# imu_ultrason_breakout.net
KiCad netlist of a schematic drawn in EAGLE
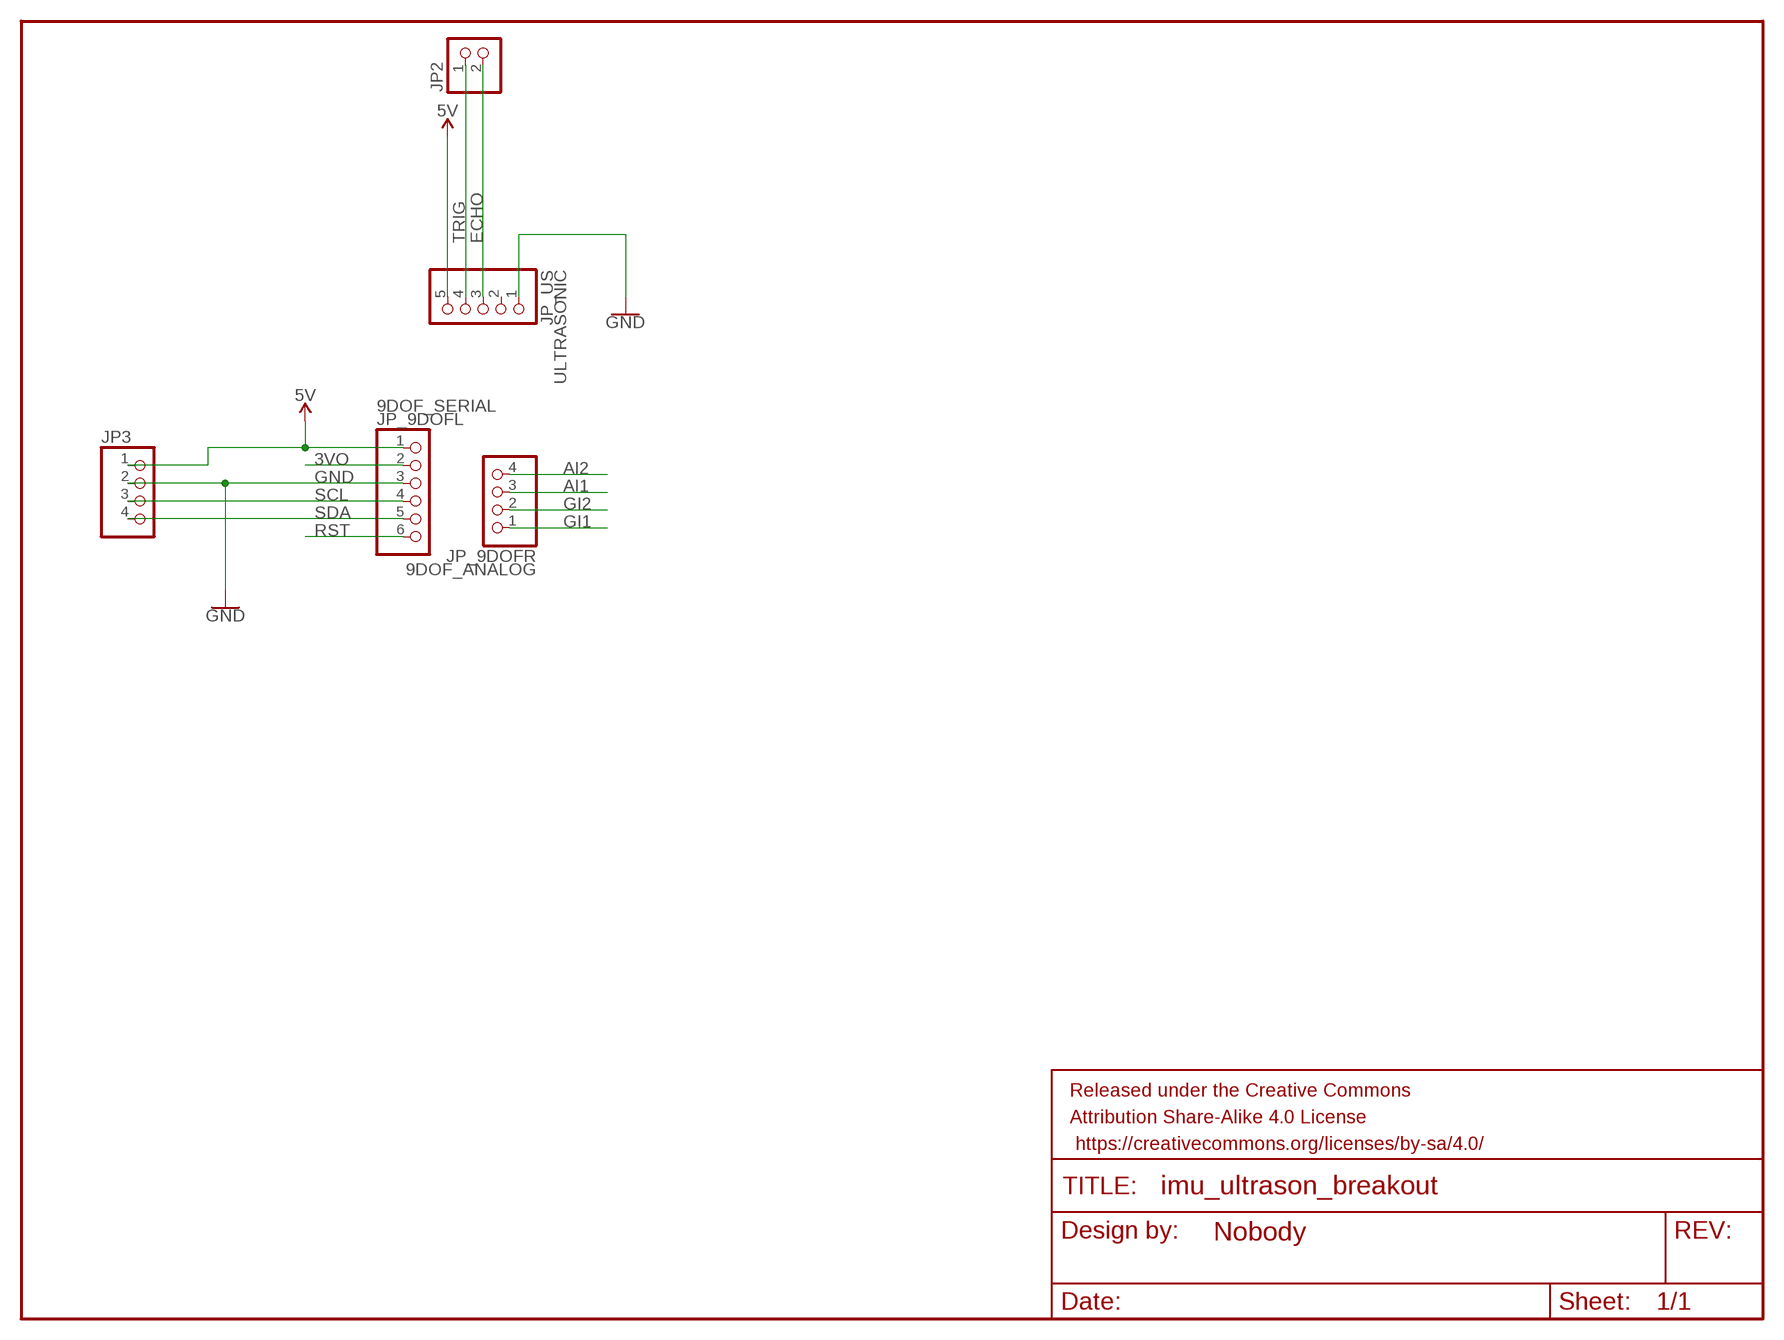
[diagram p0: schematic, sheet 1]

(export (version "E")
  (design (tool "Eeschema 10.0.6"))
  (components
    (comp (ref "FRAME1")
      (value "FRAME-LETTERNO_PACKAGE")
      (footprint "eagle-import:DUMMY")
      (fields (field (name "DESIGNER") "Nobody"))
      (libsource (lib "eagle-import") (part "FRAME-LETTERNO_PACKAGE"))
    )
    (comp (ref "JP2")
      (value "PINHD-1X2")
      (footprint "eagle-import:1X02")
      (libsource (lib "eagle-import") (part "PINHD-1X2"))
    )
    (comp (ref "JP3")
      (value "PINHD-1X4")
      (footprint "eagle-import:1X04")
      (libsource (lib "eagle-import") (part "PINHD-1X4"))
    )
    (comp (ref "JP_9DOFL")
      (value "PINHD-1X6")
      (footprint "eagle-import:1X06")
      (libsource (lib "eagle-import") (part "PINHD-1X6"))
    )
    (comp (ref "JP_9DOFR")
      (value "PINHD-1X4")
      (footprint "eagle-import:1X04")
      (libsource (lib "eagle-import") (part "PINHD-1X4"))
    )
    (comp (ref "JP_US")
      (value "PINHD-1X5")
      (footprint "eagle-import:1X05")
      (libsource (lib "eagle-import") (part "PINHD-1X5"))
    )
  )
  (nets
    (net (code "1") (name "/3VO") (class "Default")
      (node (ref "JP_9DOFL") (pin "2") (pinfunction "2_2") (pintype "passive"))
    )
    (net (code "2") (name "/AI1") (class "Default")
      (node (ref "JP_9DOFR") (pin "3") (pinfunction "3_3") (pintype "passive"))
    )
    (net (code "3") (name "/AI2") (class "Default")
      (node (ref "JP_9DOFR") (pin "4") (pinfunction "4_4") (pintype "passive"))
    )
    (net (code "4") (name "/ECHO") (class "Default")
      (node (ref "JP2") (pin "2") (pinfunction "2_2") (pintype "passive"))
      (node (ref "JP_US") (pin "3") (pinfunction "3_3") (pintype "passive"))
    )
    (net (code "5") (name "/GI1") (class "Default")
      (node (ref "JP_9DOFR") (pin "1") (pinfunction "1_1") (pintype "passive"))
    )
    (net (code "6") (name "/GI2") (class "Default")
      (node (ref "JP_9DOFR") (pin "2") (pinfunction "2_2") (pintype "passive"))
    )
    (net (code "7") (name "/RST") (class "Default")
      (node (ref "JP_9DOFL") (pin "6") (pinfunction "6_6") (pintype "passive"))
    )
    (net (code "8") (name "/SCL") (class "Default")
      (node (ref "JP3") (pin "3") (pinfunction "3_3") (pintype "passive"))
      (node (ref "JP_9DOFL") (pin "4") (pinfunction "4_4") (pintype "passive"))
    )
    (net (code "9") (name "/SDA") (class "Default")
      (node (ref "JP3") (pin "4") (pinfunction "4_4") (pintype "passive"))
      (node (ref "JP_9DOFL") (pin "5") (pinfunction "5_5") (pintype "passive"))
    )
    (net (code "10") (name "/TRIG") (class "Default")
      (node (ref "JP2") (pin "1") (pinfunction "1_1") (pintype "passive"))
      (node (ref "JP_US") (pin "4") (pinfunction "4_4") (pintype "passive"))
    )
    (net (code "11") (name "5V") (class "Default")
      (node (ref "JP3") (pin "1") (pinfunction "1_1") (pintype "passive"))
      (node (ref "JP_9DOFL") (pin "1") (pinfunction "1_1") (pintype "passive"))
      (node (ref "JP_US") (pin "5") (pinfunction "5_5") (pintype "passive"))
    )
    (net (code "12") (name "GND") (class "Default")
      (node (ref "JP3") (pin "2") (pinfunction "2_2") (pintype "passive"))
      (node (ref "JP_9DOFL") (pin "3") (pinfunction "3_3") (pintype "passive"))
      (node (ref "JP_US") (pin "1") (pinfunction "1_1") (pintype "passive"))
    )
    (net (code "13") (name "unconnected-(JP_US-Pad2)") (class "Default")
      (node (ref "JP_US") (pin "2") (pinfunction "2_2") (pintype "passive"))
    )
  )
)
